# Sheet1.net
KiCad netlist of a schematic drawn in Altium Designer
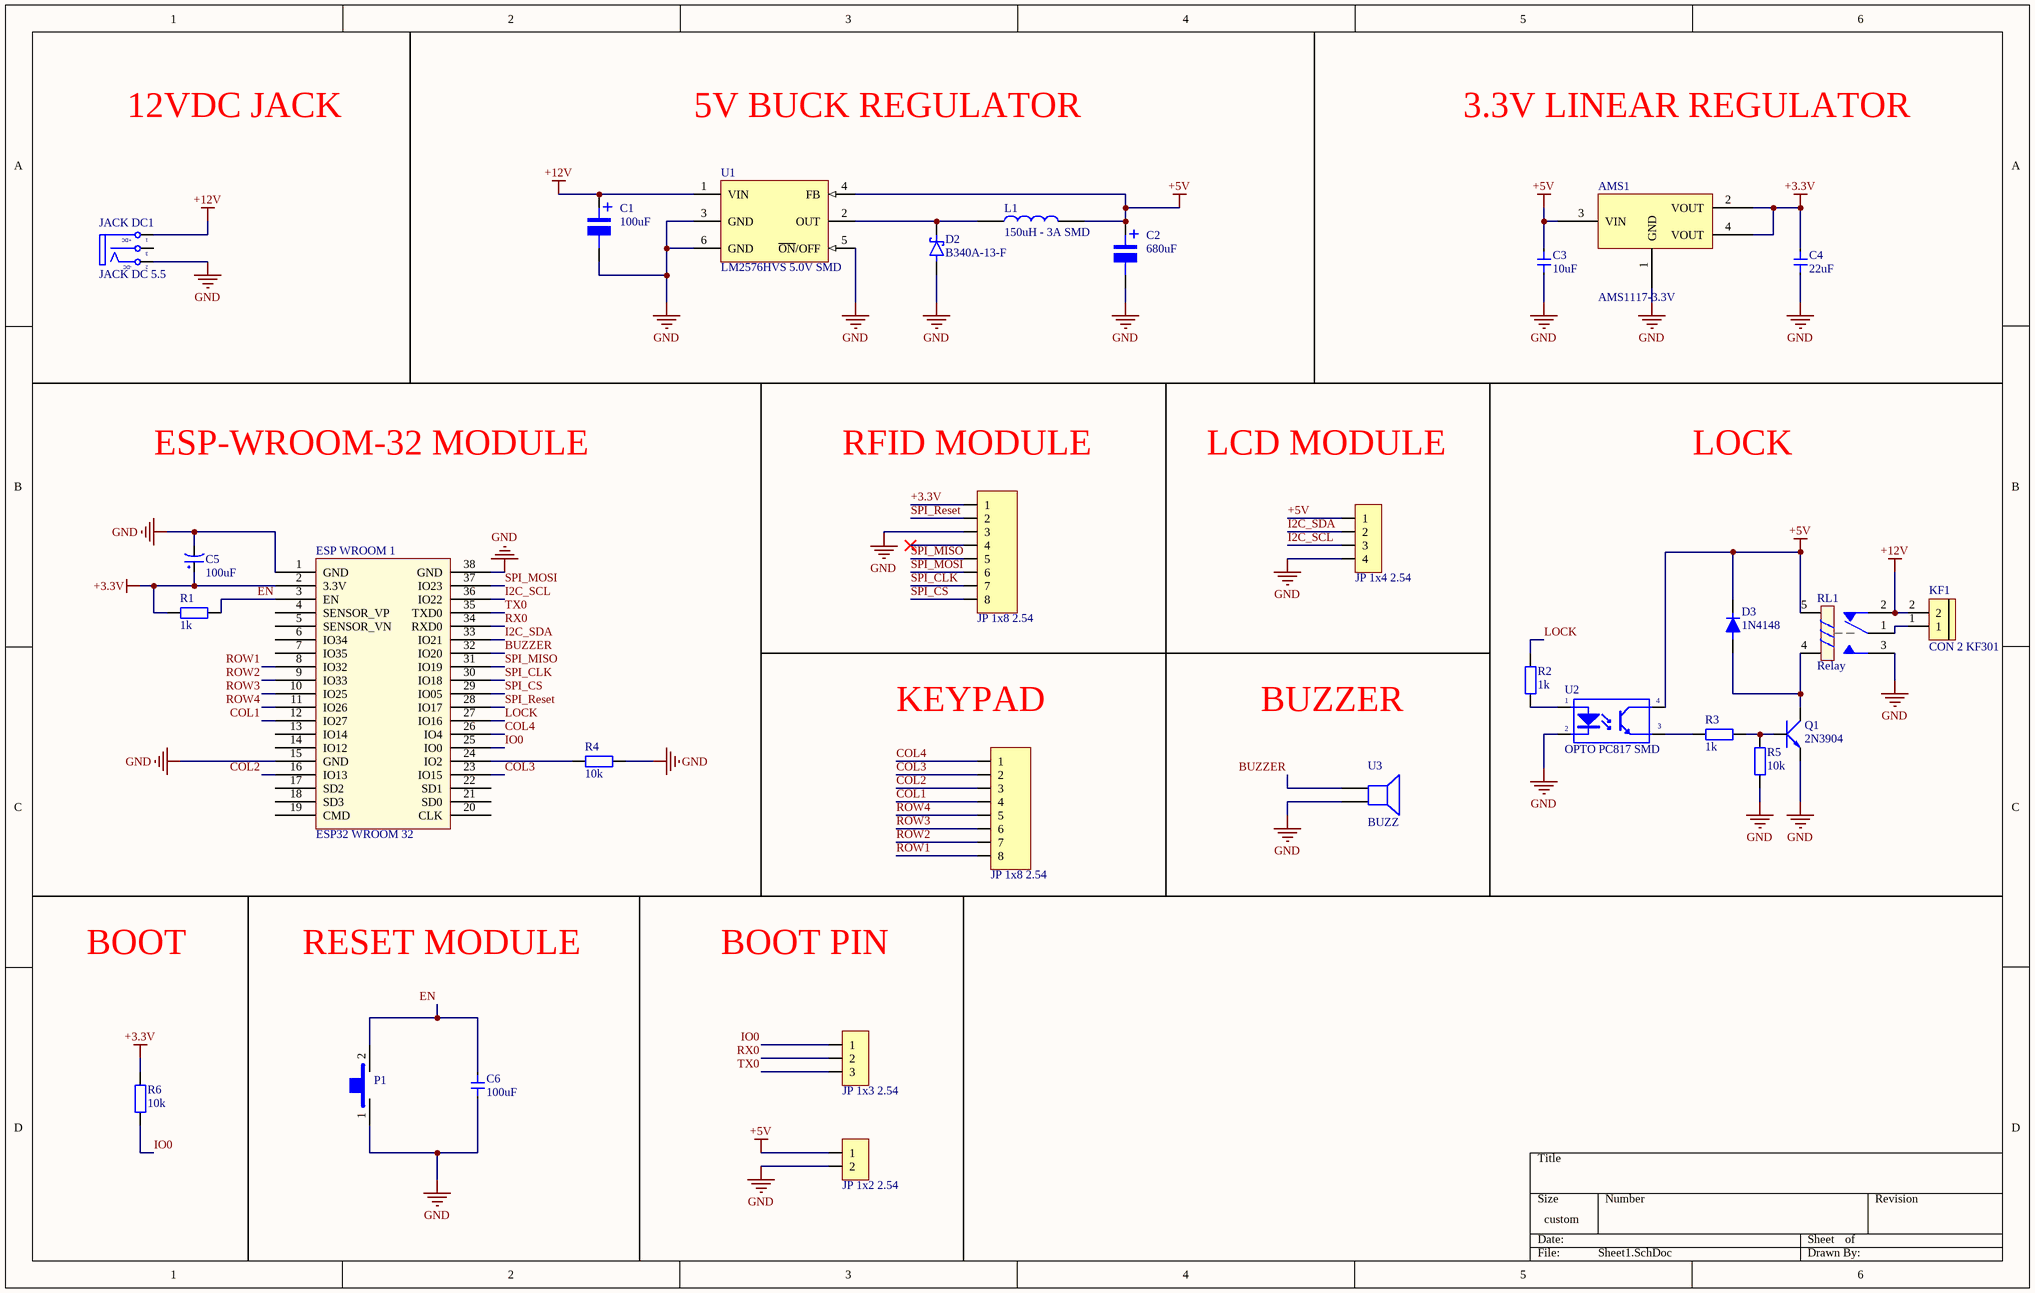
[diagram p0: Sheet1.SchDoc]

(export (version "E")
  (design (tool "Eeschema 10.0.6"))
  (components
    (comp (ref "AMS1")
      (value "AMS1117-3.3V")
      (footprint "SOT223")
      (description "Dán")
      (libsource (lib "Altium_Lib_by_KhueNguyenCreator") (part "AMS1117 SMD"))
    )
    (comp (ref "C1")
      (value "100uF")
      (footprint "tu nhom 6.3 (d)")
      (description "Dán")
      (libsource (lib "Altium_Lib_by_KhueNguyenCreator") (part "Tu Nhom 100uF 25V"))
    )
    (comp (ref "C2")
      (value "680uF")
      (footprint "tu nhom 10 (G)")
      (description "Dán")
      (libsource (lib "Altium_Lib_by_KhueNguyenCreator") (part "Tu Nhom 680uF 16V"))
    )
    (comp (ref "C3")
      (value "10uF")
      (footprint "Cap 0603")
      (description "Capacitor SMD 0603")
      (libsource (lib "Altium_Lib_by_KhueNguyenCreator") (part "Cap 0603"))
    )
    (comp (ref "C4")
      (value "22uF")
      (footprint "Cap 0603")
      (description "Capacitor SMD 0603")
      (libsource (lib "Altium_Lib_by_KhueNguyenCreator") (part "Cap 0603"))
    )
    (comp (ref "C5")
      (value "100uF")
      (footprint "tu tantalum smd3528")
      (description "Dán")
      (libsource (lib "Altium_Lib_by_KhueNguyenCreator") (part "Tu tantalum 100uF 6.3V SMD3528"))
    )
    (comp (ref "C6")
      (value "100uF")
      (footprint "Cap 0603")
      (description "Capacitor SMD 0603")
      (libsource (lib "Altium_Lib_by_KhueNguyenCreator") (part "Cap 0603"))
    )
    (comp (ref "D2")
      (value "B340A-13-F")
      (footprint "DIOM5226X240N")
      (description "Diode Schottky 40V 3A Surface Mount SMA")
      (fields (field (name "MF") "Diodes Inc."))
      (libsource (lib "Altium_Lib_by_KhueNguyenCreator") (part "B340A-13-F"))
    )
    (comp (ref "D3")
      (value "1N4148")
      (footprint "SOD-323")
      (description "DIODE GEN PURP 75V 150MA DO35")
      (libsource (lib "Howard") (part "DIODE GEN PURP 75V 150MA DO35"))
    )
    (comp (ref "ESP WROOM 1")
      (value "ESP32 WROOM 32")
      (footprint "ESP32-WROOM-32D")
      (libsource (lib "Altium_Lib_by_KhueNguyenCreator") (part "ESP32 WROOM 32"))
    )
    (comp (ref "JACK DC1")
      (value "JACK DC 5.5")
      (footprint "JACK DC 5.5")
      (libsource (lib "Altium_Lib_by_KhueNguyenCreator") (part "JACK DC 5.5"))
    )
    (comp (ref "JP1")
      (value "JP 1x8 2.54")
      (footprint "JP 1x8 CT")
      (description "Cắm")
      (libsource (lib "Altium_Lib_by_KhueNguyenCreator") (part "JP 1x8 2.54 Cai Thang"))
    )
    (comp (ref "JP2")
      (value "JP 1x4 2.54")
      (footprint "JP 1x4 CC")
      (description "Cắm")
      (libsource (lib "Altium_Lib_by_KhueNguyenCreator") (part "JP 1x4 2.54 Cai Cong"))
    )
    (comp (ref "JP3")
      (value "JP 1x8 2.54")
      (footprint "JP 1x8 CT")
      (description "Cắm")
      (libsource (lib "Altium_Lib_by_KhueNguyenCreator") (part "JP 1x8 2.54 Cai Thang"))
    )
    (comp (ref "JP4")
      (value "JP 1x3 2.54")
      (footprint "JP 1x3 DT")
      (description "Cắm")
      (libsource (lib "Altium_Lib_by_KhueNguyenCreator") (part "JP 1x3 2.54 Duc Thang"))
    )
    (comp (ref "JP5")
      (value "JP 1x2 2.54")
      (footprint "JP 1x2 DT")
      (description "Cắm")
      (libsource (lib "Altium_Lib_by_KhueNguyenCreator") (part "JP 1x2 2.54 Duc Thang"))
    )
    (comp (ref "KF1")
      (value "CON 2 KF301")
      (footprint "Con 2 KF301 5.08")
      (description "Cắm")
      (libsource (lib "Altium_Lib_by_KhueNguyenCreator") (part "CON 2 KF301"))
    )
    (comp (ref "L1")
      (value "150uH - 3A SMD")
      (footprint "Cuon Cam 12x12x10")
      (description "Dán")
      (libsource (lib "Altium_Lib_by_KhueNguyenCreator") (part "CUON CAM 100uH SMD"))
    )
    (comp (ref "P1")
      (value "~")
      (footprint "SW 2P SMD")
      (description "SMD Mini Push Button Switch 2 Pin 3x6x2.7mm")
      (fields (field (name "MPN") "SMD Mini Push Button 2 SMD"))
      (libsource (lib "BYTECH_HW_LIB_2019") (part "Button 2 SMD"))
    )
    (comp (ref "Q1")
      (value "2N3904")
      (footprint "TO92")
      (description "NPN transistor EBC")
      (libsource (lib "Altium_Lib_by_KhueNguyenCreator") (part "Trans 2N3904"))
    )
    (comp (ref "R1")
      (value "1k")
      (footprint "tro smd 0603")
      (description "Dán")
      (libsource (lib "Altium_Lib_by_KhueNguyenCreator") (part "Tro 0603 1% 1k"))
    )
    (comp (ref "R2")
      (value "1k")
      (footprint "tro smd 0603")
      (description "Dán")
      (libsource (lib "Altium_Lib_by_KhueNguyenCreator") (part "Tro 0603 1% 1k"))
    )
    (comp (ref "R3")
      (value "1k")
      (footprint "tro smd 0603")
      (description "Dán")
      (libsource (lib "Altium_Lib_by_KhueNguyenCreator") (part "Tro 0603 1% 1k"))
    )
    (comp (ref "R4")
      (value "10k")
      (footprint "tro smd 0603")
      (description "Dán")
      (libsource (lib "Altium_Lib_by_KhueNguyenCreator") (part "Tro 0603 1% 10k"))
    )
    (comp (ref "R5")
      (value "10k")
      (footprint "tro smd 0603")
      (description "Dán")
      (libsource (lib "Altium_Lib_by_KhueNguyenCreator") (part "Tro 0603 1% 10k"))
    )
    (comp (ref "R6")
      (value "10k")
      (footprint "tro smd 0603")
      (description "Dán")
      (libsource (lib "Altium_Lib_by_KhueNguyenCreator") (part "Tro 0603 1% 10k"))
    )
    (comp (ref "RL1")
      (value "Relay")
      (footprint "Relay 5 Chan SRD")
      (description "Relay 5 Chan")
      (libsource (lib "Altium_Lib_by_KhueNguyenCreator") (part "Relay 5 Chan SRD"))
    )
    (comp (ref "U1")
      (value "LM2576HVS 5.0V SMD")
      (footprint "TO263-5")
      (description "Dán")
      (libsource (lib "Altium_Lib_by_KhueNguyenCreator") (part "LM2576HVS 5.0V SMD"))
    )
    (comp (ref "U2")
      (value "OPTO PC817 SMD")
      (footprint "SOP4")
      (description "Single Opto")
      (libsource (lib "Altium_Lib_by_KhueNguyenCreator") (part "OPTO PC817 SMD"))
    )
    (comp (ref "U3")
      (value "BUZZ")
      (footprint "BUZZER_D9_TH")
      (description "Loudspeaker")
      (libsource (lib "BYTECH_HW_LIB_2019") (part "Speaker"))
    )
  )
  (nets
    (net (code "1") (name "+3.3V") (class "Default")
      (node (ref "AMS1") (pin "2") (pinfunction "VOUT_2") (pintype "passive"))
      (node (ref "AMS1") (pin "4") (pinfunction "VOUT_4") (pintype "passive"))
      (node (ref "C4") (pin "1") (pinfunction "1_1") (pintype "passive"))
      (node (ref "C5") (pin "1") (pinfunction "1_1") (pintype "passive"))
      (node (ref "ESP WROOM 1") (pin "2") (pinfunction "3.3V_2") (pintype "passive"))
      (node (ref "JP1") (pin "1") (pinfunction "1_1") (pintype "passive"))
      (node (ref "R1") (pin "2") (pinfunction "2_2") (pintype "passive"))
      (node (ref "R6") (pin "1") (pinfunction "1_1") (pintype "passive"))
    )
    (net (code "2") (name "+5V") (class "Default")
      (node (ref "AMS1") (pin "3") (pinfunction "VIN_3") (pintype "passive"))
      (node (ref "C2") (pin "1") (pinfunction "1_1") (pintype "passive"))
      (node (ref "C3") (pin "1") (pinfunction "1_1") (pintype "passive"))
      (node (ref "D3") (pin "2") (pinfunction "CATHODE_2") (pintype "passive"))
      (node (ref "JP2") (pin "1") (pinfunction "1_1") (pintype "passive"))
      (node (ref "JP5") (pin "1") (pinfunction "1_1") (pintype "passive"))
      (node (ref "L1") (pin "2") (pinfunction "2_2") (pintype "passive"))
      (node (ref "RL1") (pin "5") (pinfunction "5_5") (pintype "passive"))
      (node (ref "U1") (pin "4") (pinfunction "FB_4") (pintype "input"))
      (node (ref "U2") (pin "4") (pinfunction "C_4") (pintype "passive"))
    )
    (net (code "3") (name "+12V") (class "Default")
      (node (ref "C1") (pin "1") (pinfunction "1_1") (pintype "passive"))
      (node (ref "JACK DC1") (pin "1") (pinfunction "T_1") (pintype "passive"))
      (node (ref "KF1") (pin "2") (pinfunction "2_2") (pintype "passive"))
      (node (ref "RL1") (pin "2") (pinfunction "2_2") (pintype "passive"))
      (node (ref "U1") (pin "1") (pinfunction "VIN_1") (pintype "power_in"))
    )
    (net (code "4") (name "/BUZZER") (class "Default")
      (node (ref "ESP WROOM 1") (pin "32") (pinfunction "IO20_32") (pintype "passive"))
      (node (ref "U3") (pin "1") (pinfunction "1_1") (pintype "passive"))
    )
    (net (code "5") (name "/COL1") (class "Default")
      (node (ref "ESP WROOM 1") (pin "12") (pinfunction "IO27_12") (pintype "passive"))
      (node (ref "JP3") (pin "4") (pinfunction "4_4") (pintype "passive"))
    )
    (net (code "6") (name "/COL2") (class "Default")
      (node (ref "ESP WROOM 1") (pin "16") (pinfunction "IO13_16") (pintype "passive"))
      (node (ref "JP3") (pin "3") (pinfunction "3_3") (pintype "passive"))
    )
    (net (code "7") (name "/COL3") (class "Default")
      (node (ref "ESP WROOM 1") (pin "23") (pinfunction "IO15_23") (pintype "passive"))
      (node (ref "JP3") (pin "2") (pinfunction "2_2") (pintype "passive"))
    )
    (net (code "8") (name "/COL4") (class "Default")
      (node (ref "ESP WROOM 1") (pin "26") (pinfunction "IO4_26") (pintype "passive"))
      (node (ref "JP3") (pin "1") (pinfunction "1_1") (pintype "passive"))
    )
    (net (code "9") (name "/EN") (class "Default")
      (node (ref "C6") (pin "1") (pinfunction "1_1") (pintype "passive"))
      (node (ref "ESP WROOM 1") (pin "3") (pinfunction "EN_3") (pintype "passive"))
      (node (ref "P1") (pin "2") (pinfunction "2_2") (pintype "passive"))
      (node (ref "R1") (pin "1") (pinfunction "1_1") (pintype "passive"))
    )
    (net (code "10") (name "/I2C_SCL") (class "Default")
      (node (ref "ESP WROOM 1") (pin "36") (pinfunction "IO22_36") (pintype "passive"))
      (node (ref "JP2") (pin "3") (pinfunction "3_3") (pintype "passive"))
    )
    (net (code "11") (name "/I2C_SDA") (class "Default")
      (node (ref "ESP WROOM 1") (pin "33") (pinfunction "IO21_33") (pintype "passive"))
      (node (ref "JP2") (pin "2") (pinfunction "2_2") (pintype "passive"))
    )
    (net (code "12") (name "/IO0") (class "Default")
      (node (ref "ESP WROOM 1") (pin "25") (pinfunction "IO0_25") (pintype "passive"))
      (node (ref "JP4") (pin "1") (pinfunction "1_1") (pintype "passive"))
      (node (ref "R6") (pin "2") (pinfunction "2_2") (pintype "passive"))
    )
    (net (code "13") (name "/LOCK") (class "Default")
      (node (ref "ESP WROOM 1") (pin "27") (pinfunction "IO16_27") (pintype "passive"))
      (node (ref "R2") (pin "1") (pinfunction "1_1") (pintype "passive"))
    )
    (net (code "14") (name "/ROW1") (class "Default")
      (node (ref "ESP WROOM 1") (pin "8") (pinfunction "IO32_8") (pintype "passive"))
      (node (ref "JP3") (pin "8") (pinfunction "8_8") (pintype "passive"))
    )
    (net (code "15") (name "/ROW2") (class "Default")
      (node (ref "ESP WROOM 1") (pin "9") (pinfunction "IO33_9") (pintype "passive"))
      (node (ref "JP3") (pin "7") (pinfunction "7_7") (pintype "passive"))
    )
    (net (code "16") (name "/ROW3") (class "Default")
      (node (ref "ESP WROOM 1") (pin "10") (pinfunction "IO25_10") (pintype "passive"))
      (node (ref "JP3") (pin "6") (pinfunction "6_6") (pintype "passive"))
    )
    (net (code "17") (name "/ROW4") (class "Default")
      (node (ref "ESP WROOM 1") (pin "11") (pinfunction "IO26_11") (pintype "passive"))
      (node (ref "JP3") (pin "5") (pinfunction "5_5") (pintype "passive"))
    )
    (net (code "18") (name "/RX0") (class "Default")
      (node (ref "ESP WROOM 1") (pin "34") (pinfunction "RXD0_34") (pintype "passive"))
      (node (ref "JP4") (pin "2") (pinfunction "2_2") (pintype "passive"))
    )
    (net (code "19") (name "/SPI_CLK") (class "Default")
      (node (ref "ESP WROOM 1") (pin "30") (pinfunction "IO18_30") (pintype "passive"))
      (node (ref "JP1") (pin "7") (pinfunction "7_7") (pintype "passive"))
    )
    (net (code "20") (name "/SPI_CS") (class "Default")
      (node (ref "ESP WROOM 1") (pin "29") (pinfunction "IO05_29") (pintype "passive"))
      (node (ref "JP1") (pin "8") (pinfunction "8_8") (pintype "passive"))
    )
    (net (code "21") (name "/SPI_MISO") (class "Default")
      (node (ref "ESP WROOM 1") (pin "31") (pinfunction "IO19_31") (pintype "passive"))
      (node (ref "JP1") (pin "5") (pinfunction "5_5") (pintype "passive"))
    )
    (net (code "22") (name "/SPI_MOSI") (class "Default")
      (node (ref "ESP WROOM 1") (pin "37") (pinfunction "IO23_37") (pintype "passive"))
      (node (ref "JP1") (pin "6") (pinfunction "6_6") (pintype "passive"))
    )
    (net (code "23") (name "/SPI_Reset") (class "Default")
      (node (ref "ESP WROOM 1") (pin "28") (pinfunction "IO17_28") (pintype "passive"))
      (node (ref "JP1") (pin "2") (pinfunction "2_2") (pintype "passive"))
    )
    (net (code "24") (name "/TX0") (class "Default")
      (node (ref "ESP WROOM 1") (pin "35") (pinfunction "TXD0_35") (pintype "passive"))
      (node (ref "JP4") (pin "3") (pinfunction "3_3") (pintype "passive"))
    )
    (net (code "25") (name "GND") (class "Default")
      (node (ref "AMS1") (pin "1") (pinfunction "GND_1") (pintype "passive"))
      (node (ref "C1") (pin "2") (pinfunction "2_2") (pintype "passive"))
      (node (ref "C2") (pin "2") (pinfunction "2_2") (pintype "passive"))
      (node (ref "C3") (pin "2") (pinfunction "2_2") (pintype "passive"))
      (node (ref "C4") (pin "2") (pinfunction "2_2") (pintype "passive"))
      (node (ref "C5") (pin "2") (pinfunction "2_2") (pintype "passive"))
      (node (ref "C6") (pin "2") (pinfunction "2_2") (pintype "passive"))
      (node (ref "D2") (pin "A") (pinfunction "A_A") (pintype "passive"))
      (node (ref "ESP WROOM 1") (pin "1") (pinfunction "GND_1") (pintype "passive"))
      (node (ref "ESP WROOM 1") (pin "15") (pinfunction "GND_15") (pintype "passive"))
      (node (ref "ESP WROOM 1") (pin "38") (pinfunction "GND_38") (pintype "passive"))
      (node (ref "JACK DC1") (pin "2") (pinfunction "TN_2") (pintype "passive"))
      (node (ref "JP1") (pin "3") (pinfunction "3_3") (pintype "passive"))
      (node (ref "JP2") (pin "4") (pinfunction "4_4") (pintype "passive"))
      (node (ref "JP5") (pin "2") (pinfunction "2_2") (pintype "passive"))
      (node (ref "P1") (pin "1") (pinfunction "1_1") (pintype "passive"))
      (node (ref "Q1") (pin "1") (pinfunction "E_1") (pintype "passive"))
      (node (ref "R4") (pin "1") (pinfunction "1_1") (pintype "passive"))
      (node (ref "R5") (pin "1") (pinfunction "1_1") (pintype "passive"))
      (node (ref "RL1") (pin "3") (pinfunction "3_3") (pintype "passive"))
      (node (ref "U1") (pin "3") (pinfunction "GND_3") (pintype "power_in"))
      (node (ref "U1") (pin "5") (pinfunction "~{ON}/OFF_5") (pintype "input"))
      (node (ref "U1") (pin "6") (pinfunction "GND_6") (pintype "passive"))
      (node (ref "U2") (pin "2") (pinfunction "K_2") (pintype "passive"))
      (node (ref "U3") (pin "2") (pinfunction "2_2") (pintype "passive"))
    )
    (net (code "26") (name "Net-(D3-ANODE)") (class "Default")
      (node (ref "D3") (pin "1") (pinfunction "ANODE_1") (pintype "passive"))
      (node (ref "Q1") (pin "3") (pinfunction "C_3") (pintype "passive"))
      (node (ref "RL1") (pin "4") (pinfunction "4_4") (pintype "passive"))
    )
    (net (code "27") (name "Net-(ESP WROOM 1-IO2)") (class "Default")
      (node (ref "ESP WROOM 1") (pin "24") (pinfunction "IO2_24") (pintype "passive"))
      (node (ref "R4") (pin "2") (pinfunction "2_2") (pintype "passive"))
    )
    (net (code "28") (name "Net-(KF1-Pad1)") (class "Default")
      (node (ref "KF1") (pin "1") (pinfunction "1_1") (pintype "passive"))
      (node (ref "RL1") (pin "1") (pinfunction "1_1") (pintype "passive"))
    )
    (net (code "29") (name "Net-(Q1-B)") (class "Default")
      (node (ref "Q1") (pin "2") (pinfunction "B_2") (pintype "passive"))
      (node (ref "R3") (pin "2") (pinfunction "2_2") (pintype "passive"))
      (node (ref "R5") (pin "2") (pinfunction "2_2") (pintype "passive"))
    )
    (net (code "30") (name "Net-(U1-OUT)") (class "Default")
      (node (ref "D2") (pin "C") (pinfunction "C_C") (pintype "passive"))
      (node (ref "L1") (pin "1") (pinfunction "1_1") (pintype "passive"))
      (node (ref "U1") (pin "2") (pinfunction "OUT_2") (pintype "power_in"))
    )
    (net (code "31") (name "Net-(U2-A)") (class "Default")
      (node (ref "R2") (pin "2") (pinfunction "2_2") (pintype "passive"))
      (node (ref "U2") (pin "1") (pinfunction "A_1") (pintype "passive"))
    )
    (net (code "32") (name "Net-(U2-E)") (class "Default")
      (node (ref "R3") (pin "1") (pinfunction "1_1") (pintype "passive"))
      (node (ref "U2") (pin "3") (pinfunction "E_3") (pintype "passive"))
    )
    (net (code "33") (name "unconnected-(ESP WROOM 1-CLK-Pad20)") (class "Default")
      (node (ref "ESP WROOM 1") (pin "20") (pinfunction "CLK_20") (pintype "passive"))
    )
    (net (code "34") (name "unconnected-(ESP WROOM 1-CMD-Pad19)") (class "Default")
      (node (ref "ESP WROOM 1") (pin "19") (pinfunction "CMD_19") (pintype "passive"))
    )
    (net (code "35") (name "unconnected-(ESP WROOM 1-IO12-Pad14)") (class "Default")
      (node (ref "ESP WROOM 1") (pin "14") (pinfunction "IO12_14") (pintype "passive"))
    )
    (net (code "36") (name "unconnected-(ESP WROOM 1-IO14-Pad13)") (class "Default")
      (node (ref "ESP WROOM 1") (pin "13") (pinfunction "IO14_13") (pintype "passive"))
    )
    (net (code "37") (name "unconnected-(ESP WROOM 1-IO34-Pad6)") (class "Default")
      (node (ref "ESP WROOM 1") (pin "6") (pinfunction "IO34_6") (pintype "passive"))
    )
    (net (code "38") (name "unconnected-(ESP WROOM 1-IO35-Pad7)") (class "Default")
      (node (ref "ESP WROOM 1") (pin "7") (pinfunction "IO35_7") (pintype "passive"))
    )
    (net (code "39") (name "unconnected-(ESP WROOM 1-SD0-Pad21)") (class "Default")
      (node (ref "ESP WROOM 1") (pin "21") (pinfunction "SD0_21") (pintype "passive"))
    )
    (net (code "40") (name "unconnected-(ESP WROOM 1-SD1-Pad22)") (class "Default")
      (node (ref "ESP WROOM 1") (pin "22") (pinfunction "SD1_22") (pintype "passive"))
    )
    (net (code "41") (name "unconnected-(ESP WROOM 1-SD2-Pad17)") (class "Default")
      (node (ref "ESP WROOM 1") (pin "17") (pinfunction "SD2_17") (pintype "passive"))
    )
    (net (code "42") (name "unconnected-(ESP WROOM 1-SD3-Pad18)") (class "Default")
      (node (ref "ESP WROOM 1") (pin "18") (pinfunction "SD3_18") (pintype "passive"))
    )
    (net (code "43") (name "unconnected-(ESP WROOM 1-SENSOR_VN-Pad5)") (class "Default")
      (node (ref "ESP WROOM 1") (pin "5") (pinfunction "SENSOR_VN_5") (pintype "passive"))
    )
    (net (code "44") (name "unconnected-(ESP WROOM 1-SENSOR_VP-Pad4)") (class "Default")
      (node (ref "ESP WROOM 1") (pin "4") (pinfunction "SENSOR_VP_4") (pintype "passive"))
    )
    (net (code "45") (name "unconnected-(JACK DC1-S-Pad3)") (class "Default")
      (node (ref "JACK DC1") (pin "3") (pinfunction "S_3") (pintype "power_in"))
    )
    (net (code "46") (name "unconnected-(JP1-Pad4)") (class "Default")
      (node (ref "JP1") (pin "4") (pinfunction "4_4") (pintype "passive+no_connect"))
    )
  )
)
